# teensy-jst_01.net
KiCad netlist of a schematic drawn in EAGLE
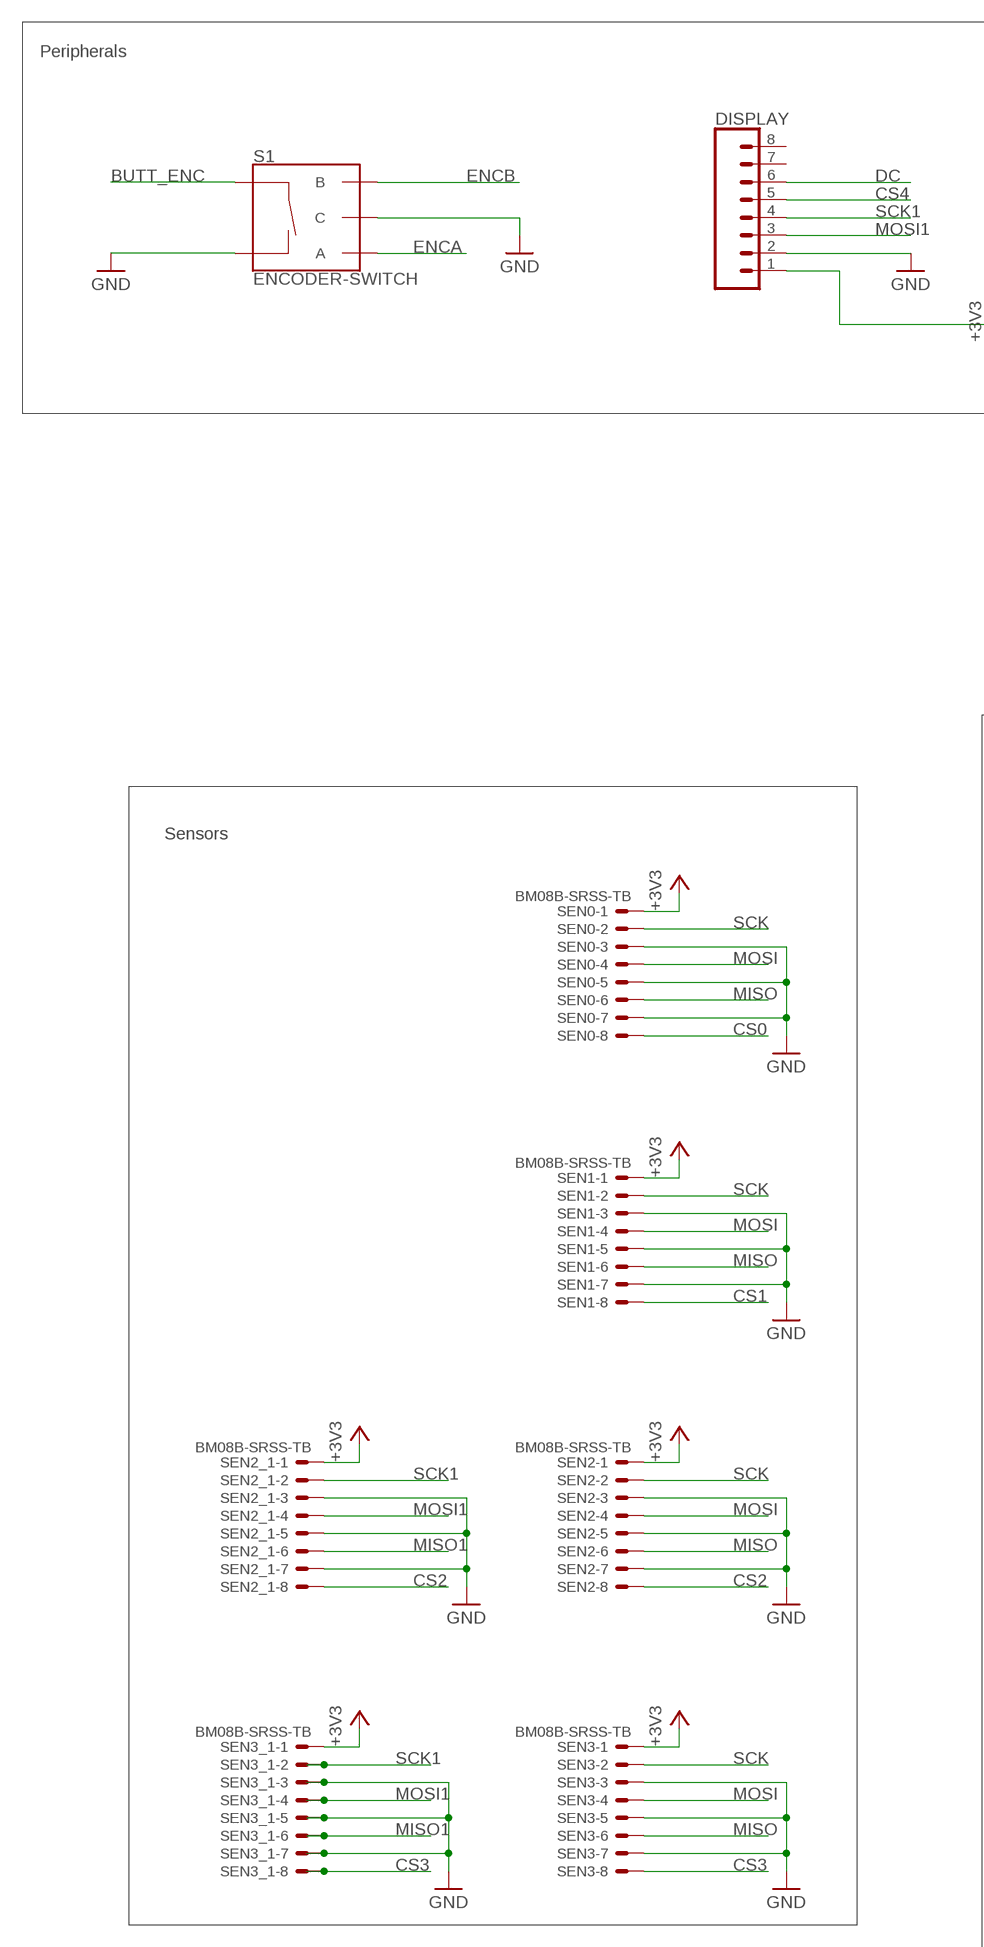
[diagram p0: schematic, sheet 1, part 1 of 2]
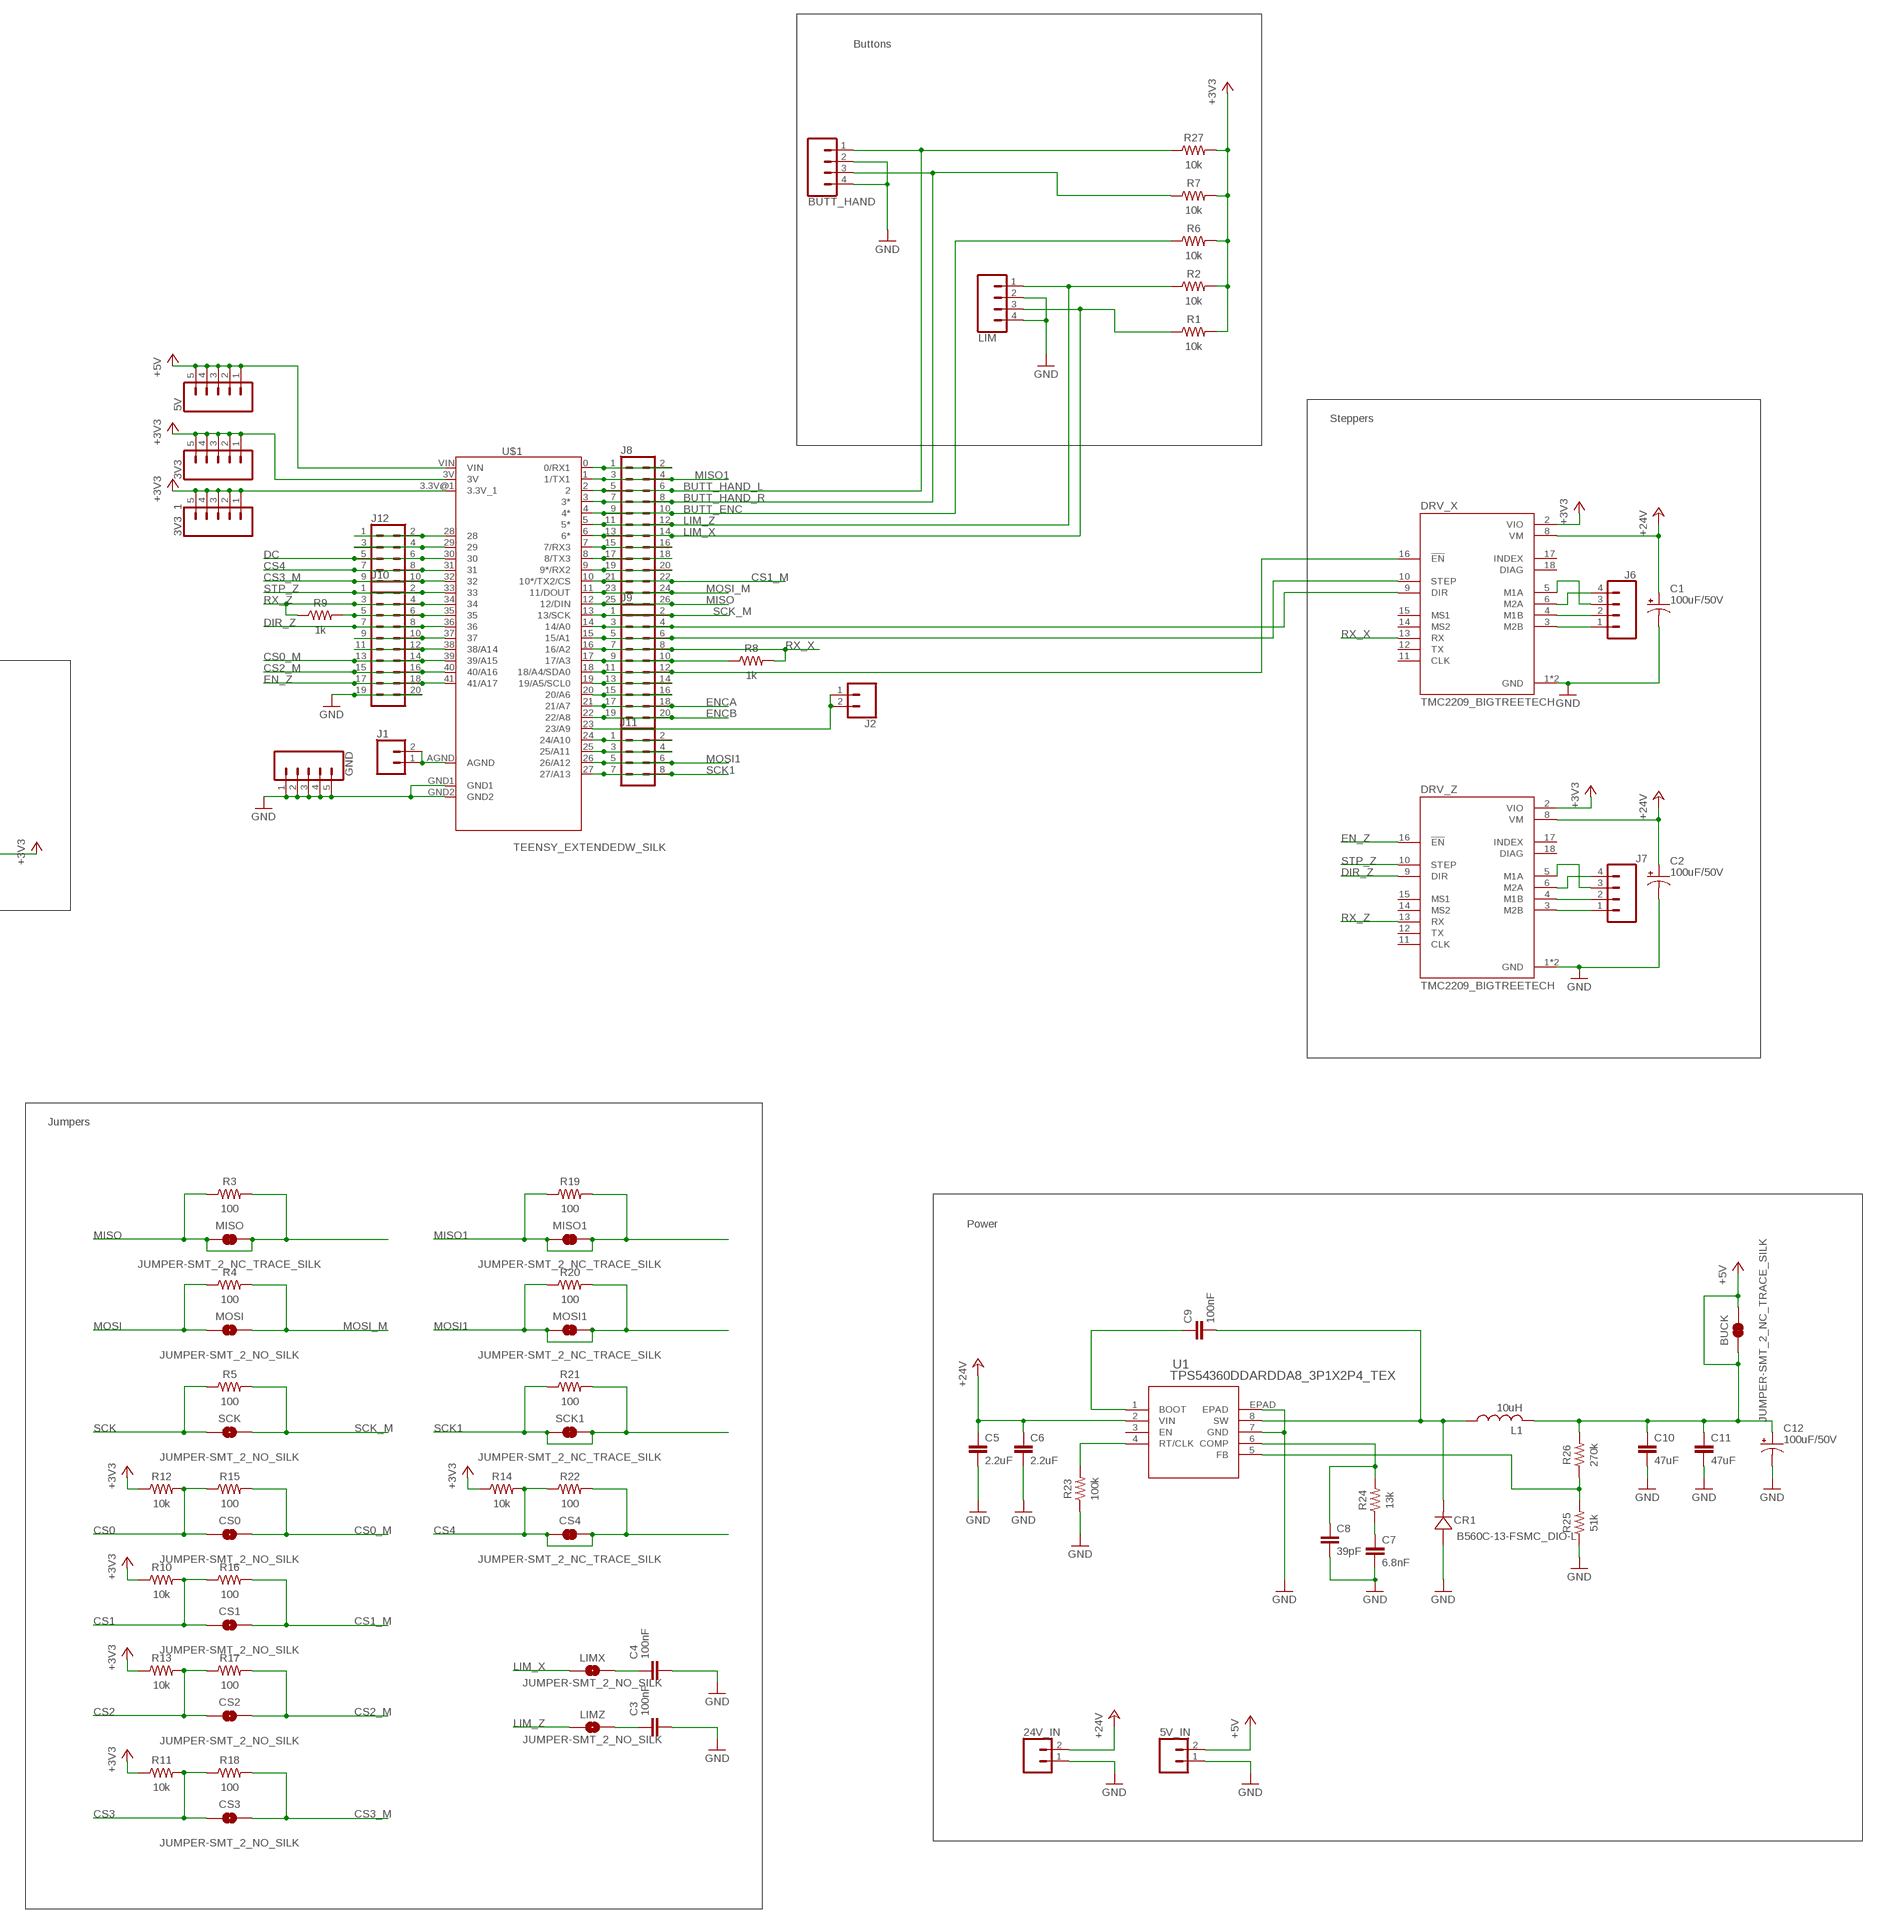
[diagram p1: schematic, sheet 1, part 2 of 2]

(export (version "E")
  (design (tool "Eeschema 10.0.6"))
  (components
    (comp (ref "3V3")
      (value "CONN_05PTH")
      (footprint "eagle-import:1X05")
      (libsource (lib "eagle-import") (part "CONN_05PTH"))
    )
    (comp (ref "3V3_1")
      (value "CONN_05PTH")
      (footprint "eagle-import:1X05")
      (libsource (lib "eagle-import") (part "CONN_05PTH"))
    )
    (comp (ref "5V")
      (value "CONN_05PTH")
      (footprint "eagle-import:1X05")
      (libsource (lib "eagle-import") (part "CONN_05PTH"))
    )
    (comp (ref "5V_IN")
      (value "CONN_025MM")
      (footprint "eagle-import:SCREWTERMINAL-5MM-2")
      (libsource (lib "eagle-import") (part "CONN_025MM"))
    )
    (comp (ref "24V_IN")
      (value "CONN_025MM")
      (footprint "eagle-import:SCREWTERMINAL-5MM-2")
      (libsource (lib "eagle-import") (part "CONN_025MM"))
    )
    (comp (ref "BUCK")
      (value "JUMPER-SMT_2_NC_TRACE_SILK")
      (footprint "eagle-import:SMT-JUMPER_2_NC_TRACE_SILK")
      (libsource (lib "eagle-import") (part "JUMPER-SMT_2_NC_TRACE_SILK"))
    )
    (comp (ref "BUTT_HAND")
      (value "CONN_041X04_NO_SILK")
      (footprint "eagle-import:1X04_NO_SILK")
      (libsource (lib "eagle-import") (part "CONN_041X04_NO_SILK"))
    )
    (comp (ref "C1")
      (value "100uF/50V")
      (footprint "eagle-import:E5-6")
      (libsource (lib "eagle-import") (part "CPOL-USE5-6"))
    )
    (comp (ref "C2")
      (value "100uF/50V")
      (footprint "eagle-import:E5-6")
      (libsource (lib "eagle-import") (part "CPOL-USE5-6"))
    )
    (comp (ref "C3")
      (value "100nF")
      (footprint "eagle-import:C0603")
      (libsource (lib "eagle-import") (part "C-EUC0603"))
    )
    (comp (ref "C4")
      (value "100nF")
      (footprint "eagle-import:C0603")
      (libsource (lib "eagle-import") (part "C-EUC0603"))
    )
    (comp (ref "C5")
      (value "2.2uF")
      (footprint "eagle-import:C0603")
      (libsource (lib "eagle-import") (part "C-EUC0603"))
    )
    (comp (ref "C6")
      (value "2.2uF")
      (footprint "eagle-import:C0603")
      (libsource (lib "eagle-import") (part "C-EUC0603"))
    )
    (comp (ref "C7")
      (value "6.8nF")
      (footprint "eagle-import:C0402")
      (libsource (lib "eagle-import") (part "C-EUC0402"))
    )
    (comp (ref "C8")
      (value "39pF")
      (footprint "eagle-import:C0402")
      (libsource (lib "eagle-import") (part "C-EUC0402"))
    )
    (comp (ref "C9")
      (value "100nF")
      (footprint "eagle-import:C0402")
      (libsource (lib "eagle-import") (part "C-EUC0402"))
    )
    (comp (ref "C10")
      (value "47uF")
      (footprint "eagle-import:C0603")
      (libsource (lib "eagle-import") (part "C-EUC0603"))
    )
    (comp (ref "C11")
      (value "47uF")
      (footprint "eagle-import:C0603")
      (libsource (lib "eagle-import") (part "C-EUC0603"))
    )
    (comp (ref "C12")
      (value "100uF/50V")
      (footprint "eagle-import:E5-6")
      (libsource (lib "eagle-import") (part "CPOL-USE5-6"))
    )
    (comp (ref "CR1")
      (value "B560C-13-FSMC_DIO-L")
      (footprint "eagle-import:SMC_DIO-L")
      (fields
        (field (name "MANUFACTURER_PART_NUMBER") "B560C-13-F")
        (field (name "COPYRIGHT") "Copyright (C) 2024 Ultra Librarian. All rights reserved.")
      )
      (libsource (lib "eagle-import") (part "B560C-13-FSMC_DIO-L"))
    )
    (comp (ref "CS0")
      (value "JUMPER-SMT_2_NO_SILK")
      (footprint "eagle-import:SMT-JUMPER_2_NO_SILK")
      (libsource (lib "eagle-import") (part "JUMPER-SMT_2_NO_SILK"))
    )
    (comp (ref "CS1")
      (value "JUMPER-SMT_2_NO_SILK")
      (footprint "eagle-import:SMT-JUMPER_2_NO_SILK")
      (libsource (lib "eagle-import") (part "JUMPER-SMT_2_NO_SILK"))
    )
    (comp (ref "CS2")
      (value "JUMPER-SMT_2_NO_SILK")
      (footprint "eagle-import:SMT-JUMPER_2_NO_SILK")
      (libsource (lib "eagle-import") (part "JUMPER-SMT_2_NO_SILK"))
    )
    (comp (ref "CS3")
      (value "JUMPER-SMT_2_NO_SILK")
      (footprint "eagle-import:SMT-JUMPER_2_NO_SILK")
      (libsource (lib "eagle-import") (part "JUMPER-SMT_2_NO_SILK"))
    )
    (comp (ref "CS4")
      (value "JUMPER-SMT_2_NC_TRACE_SILK")
      (footprint "eagle-import:SMT-JUMPER_2_NC_TRACE_SILK")
      (libsource (lib "eagle-import") (part "JUMPER-SMT_2_NC_TRACE_SILK"))
    )
    (comp (ref "DISPLAY")
      (value "CONN_08\"")
      (footprint "eagle-import:1X08")
      (libsource (lib "eagle-import") (part "CONN_08{dblquote}"))
    )
    (comp (ref "DRV_X")
      (value "TMC2209_BIGTREETECH")
      (footprint "eagle-import:MODULE_TMC2209_BIGTREETECH")
      (fields
        (field (name "MF") "Trinamic Motion Control GmbH")
        (field (name "MP") "TMC2209 SILENTSTEPSTICK")
      )
      (libsource (lib "eagle-import") (part "TMC2209_BIGTREETECH"))
    )
    (comp (ref "DRV_Z")
      (value "TMC2209_BIGTREETECH")
      (footprint "eagle-import:MODULE_TMC2209_BIGTREETECH")
      (fields
        (field (name "MF") "Trinamic Motion Control GmbH")
        (field (name "MP") "TMC2209 SILENTSTEPSTICK")
      )
      (libsource (lib "eagle-import") (part "TMC2209_BIGTREETECH"))
    )
    (comp (ref "GND")
      (value "CONN_05PTH")
      (footprint "eagle-import:1X05")
      (libsource (lib "eagle-import") (part "CONN_05PTH"))
    )
    (comp (ref "J1")
      (value "CONN_02")
      (footprint "eagle-import:1X02")
      (libsource (lib "eagle-import") (part "CONN_02"))
    )
    (comp (ref "J2")
      (value "CONN_02")
      (footprint "eagle-import:1X02")
      (libsource (lib "eagle-import") (part "CONN_02"))
    )
    (comp (ref "J6")
      (value "CONN_04PTH")
      (footprint "eagle-import:1X04")
      (libsource (lib "eagle-import") (part "CONN_04PTH"))
    )
    (comp (ref "J7")
      (value "CONN_04PTH")
      (footprint "eagle-import:1X04")
      (libsource (lib "eagle-import") (part "CONN_04PTH"))
    )
    (comp (ref "J8")
      (value "CONN_13X22X13")
      (footprint "eagle-import:2X13")
      (libsource (lib "eagle-import") (part "CONN_13X22X13"))
    )
    (comp (ref "J9")
      (value "CONN_10X2")
      (footprint "eagle-import:2X10")
      (libsource (lib "eagle-import") (part "CONN_10X2"))
    )
    (comp (ref "J10")
      (value "CONN_10X2")
      (footprint "eagle-import:2X10")
      (libsource (lib "eagle-import") (part "CONN_10X2"))
    )
    (comp (ref "J11")
      (value "CONN_04X2")
      (footprint "eagle-import:2X4")
      (libsource (lib "eagle-import") (part "CONN_04X2"))
    )
    (comp (ref "J12")
      (value "CONN_05X2PTH")
      (footprint "eagle-import:2X5")
      (libsource (lib "eagle-import") (part "CONN_05X2PTH"))
    )
    (comp (ref "L1")
      (value "10uH")
      (footprint "eagle-import:MWSA0503S-100MT")
      (libsource (lib "eagle-import") (part "L-USMWSA0503S-100MT"))
    )
    (comp (ref "LIM")
      (value "CONN_041X04_NO_SILK")
      (footprint "eagle-import:1X04_NO_SILK")
      (libsource (lib "eagle-import") (part "CONN_041X04_NO_SILK"))
    )
    (comp (ref "LIMX")
      (value "JUMPER-SMT_2_NO_SILK")
      (footprint "eagle-import:SMT-JUMPER_2_NO_SILK")
      (libsource (lib "eagle-import") (part "JUMPER-SMT_2_NO_SILK"))
    )
    (comp (ref "LIMZ")
      (value "JUMPER-SMT_2_NO_SILK")
      (footprint "eagle-import:SMT-JUMPER_2_NO_SILK")
      (libsource (lib "eagle-import") (part "JUMPER-SMT_2_NO_SILK"))
    )
    (comp (ref "MISO")
      (value "JUMPER-SMT_2_NC_TRACE_SILK")
      (footprint "eagle-import:SMT-JUMPER_2_NC_TRACE_SILK")
      (libsource (lib "eagle-import") (part "JUMPER-SMT_2_NC_TRACE_SILK"))
    )
    (comp (ref "MISO1")
      (value "JUMPER-SMT_2_NC_TRACE_SILK")
      (footprint "eagle-import:SMT-JUMPER_2_NC_TRACE_SILK")
      (libsource (lib "eagle-import") (part "JUMPER-SMT_2_NC_TRACE_SILK"))
    )
    (comp (ref "MOSI")
      (value "JUMPER-SMT_2_NO_SILK")
      (footprint "eagle-import:SMT-JUMPER_2_NO_SILK")
      (libsource (lib "eagle-import") (part "JUMPER-SMT_2_NO_SILK"))
    )
    (comp (ref "MOSI1")
      (value "JUMPER-SMT_2_NC_TRACE_SILK")
      (footprint "eagle-import:SMT-JUMPER_2_NC_TRACE_SILK")
      (libsource (lib "eagle-import") (part "JUMPER-SMT_2_NC_TRACE_SILK"))
    )
    (comp (ref "R1")
      (value "10k")
      (footprint "eagle-import:RESC1608X60")
      (libsource (lib "eagle-import") (part "R-USCHIP-0603(1608-METRIC)_"))
    )
    (comp (ref "R2")
      (value "10k")
      (footprint "eagle-import:RESC1608X60")
      (libsource (lib "eagle-import") (part "R-USCHIP-0603(1608-METRIC)_"))
    )
    (comp (ref "R3")
      (value "100")
      (footprint "eagle-import:RESC1608X60")
      (libsource (lib "eagle-import") (part "R-USCHIP-0603(1608-METRIC)_"))
    )
    (comp (ref "R4")
      (value "100")
      (footprint "eagle-import:RESC1608X60")
      (libsource (lib "eagle-import") (part "R-USCHIP-0603(1608-METRIC)_"))
    )
    (comp (ref "R5")
      (value "100")
      (footprint "eagle-import:RESC1608X60")
      (libsource (lib "eagle-import") (part "R-USCHIP-0603(1608-METRIC)_"))
    )
    (comp (ref "R6")
      (value "10k")
      (footprint "eagle-import:RESC1608X60")
      (libsource (lib "eagle-import") (part "R-USCHIP-0603(1608-METRIC)_"))
    )
    (comp (ref "R7")
      (value "10k")
      (footprint "eagle-import:RESC1608X60")
      (libsource (lib "eagle-import") (part "R-USCHIP-0603(1608-METRIC)_"))
    )
    (comp (ref "R8")
      (value "1k")
      (footprint "eagle-import:RESC1608X60")
      (libsource (lib "eagle-import") (part "R-USCHIP-0603(1608-METRIC)_"))
    )
    (comp (ref "R9")
      (value "1k")
      (footprint "eagle-import:RESC1608X60")
      (libsource (lib "eagle-import") (part "R-USCHIP-0603(1608-METRIC)_"))
    )
    (comp (ref "R10")
      (value "10k")
      (footprint "eagle-import:RESC1608X60")
      (libsource (lib "eagle-import") (part "R-USCHIP-0603(1608-METRIC)_"))
    )
    (comp (ref "R11")
      (value "10k")
      (footprint "eagle-import:RESC1608X60")
      (libsource (lib "eagle-import") (part "R-USCHIP-0603(1608-METRIC)_"))
    )
    (comp (ref "R12")
      (value "10k")
      (footprint "eagle-import:RESC1608X60")
      (libsource (lib "eagle-import") (part "R-USCHIP-0603(1608-METRIC)_"))
    )
    (comp (ref "R13")
      (value "10k")
      (footprint "eagle-import:RESC1608X60")
      (libsource (lib "eagle-import") (part "R-USCHIP-0603(1608-METRIC)_"))
    )
    (comp (ref "R14")
      (value "10k")
      (footprint "eagle-import:RESC1608X60")
      (libsource (lib "eagle-import") (part "R-USCHIP-0603(1608-METRIC)_"))
    )
    (comp (ref "R15")
      (value "100")
      (footprint "eagle-import:RESC1608X60")
      (libsource (lib "eagle-import") (part "R-USCHIP-0603(1608-METRIC)_"))
    )
    (comp (ref "R16")
      (value "100")
      (footprint "eagle-import:RESC1608X60")
      (libsource (lib "eagle-import") (part "R-USCHIP-0603(1608-METRIC)_"))
    )
    (comp (ref "R17")
      (value "100")
      (footprint "eagle-import:RESC1608X60")
      (libsource (lib "eagle-import") (part "R-USCHIP-0603(1608-METRIC)_"))
    )
    (comp (ref "R18")
      (value "100")
      (footprint "eagle-import:RESC1608X60")
      (libsource (lib "eagle-import") (part "R-USCHIP-0603(1608-METRIC)_"))
    )
    (comp (ref "R19")
      (value "100")
      (footprint "eagle-import:RESC1608X60")
      (libsource (lib "eagle-import") (part "R-USCHIP-0603(1608-METRIC)_"))
    )
    (comp (ref "R20")
      (value "100")
      (footprint "eagle-import:RESC1608X60")
      (libsource (lib "eagle-import") (part "R-USCHIP-0603(1608-METRIC)_"))
    )
    (comp (ref "R21")
      (value "100")
      (footprint "eagle-import:RESC1608X60")
      (libsource (lib "eagle-import") (part "R-USCHIP-0603(1608-METRIC)_"))
    )
    (comp (ref "R22")
      (value "100")
      (footprint "eagle-import:RESC1608X60")
      (libsource (lib "eagle-import") (part "R-USCHIP-0603(1608-METRIC)_"))
    )
    (comp (ref "R23")
      (value "100k")
      (footprint "eagle-import:RESC1005X40")
      (libsource (lib "eagle-import") (part "R-USCHIP-0402(1005-METRIC)_"))
    )
    (comp (ref "R24")
      (value "13k")
      (footprint "eagle-import:RESC1005X40")
      (libsource (lib "eagle-import") (part "R-USCHIP-0402(1005-METRIC)_"))
    )
    (comp (ref "R25")
      (value "51k")
      (footprint "eagle-import:RESC1005X40")
      (libsource (lib "eagle-import") (part "R-USCHIP-0402(1005-METRIC)_"))
    )
    (comp (ref "R26")
      (value "270k")
      (footprint "eagle-import:RESC1005X40")
      (libsource (lib "eagle-import") (part "R-USCHIP-0402(1005-METRIC)_"))
    )
    (comp (ref "R27")
      (value "10k")
      (footprint "eagle-import:RESC1608X60")
      (libsource (lib "eagle-import") (part "R-USCHIP-0603(1608-METRIC)_"))
    )
    (comp (ref "S1")
      (value "ENCODER-SWITCH")
      (footprint "eagle-import:ROTARY_ENC_PLAIN")
      (libsource (lib "eagle-import") (part "ENCODER-SWITCH"))
    )
    (comp (ref "SCK")
      (value "JUMPER-SMT_2_NO_SILK")
      (footprint "eagle-import:SMT-JUMPER_2_NO_SILK")
      (libsource (lib "eagle-import") (part "JUMPER-SMT_2_NO_SILK"))
    )
    (comp (ref "SCK1")
      (value "JUMPER-SMT_2_NC_TRACE_SILK")
      (footprint "eagle-import:SMT-JUMPER_2_NC_TRACE_SILK")
      (libsource (lib "eagle-import") (part "JUMPER-SMT_2_NC_TRACE_SILK"))
    )
    (comp (ref "SEN0")
      (value "BM08B-SRSS-TB")
      (footprint "eagle-import:BM08B-SRSS-TB")
      (libsource (lib "eagle-import") (part "?M08B-SRSS-TBB"))
    )
    (comp (ref "SEN1")
      (value "BM08B-SRSS-TB")
      (footprint "eagle-import:BM08B-SRSS-TB")
      (libsource (lib "eagle-import") (part "?M08B-SRSS-TBB"))
    )
    (comp (ref "SEN2")
      (value "BM08B-SRSS-TB")
      (footprint "eagle-import:BM08B-SRSS-TB")
      (libsource (lib "eagle-import") (part "?M08B-SRSS-TBB"))
    )
    (comp (ref "SEN2_1")
      (value "BM08B-SRSS-TB")
      (footprint "eagle-import:BM08B-SRSS-TB")
      (libsource (lib "eagle-import") (part "?M08B-SRSS-TBB"))
    )
    (comp (ref "SEN3")
      (value "BM08B-SRSS-TB")
      (footprint "eagle-import:BM08B-SRSS-TB")
      (libsource (lib "eagle-import") (part "?M08B-SRSS-TBB"))
    )
    (comp (ref "SEN3_1")
      (value "BM08B-SRSS-TB")
      (footprint "eagle-import:BM08B-SRSS-TB")
      (libsource (lib "eagle-import") (part "?M08B-SRSS-TBB"))
    )
    (comp (ref "U$1")
      (value "TEENSY_EXTENDEDW_SILK")
      (footprint "eagle-import:TEENSY_EXTENDED")
      (libsource (lib "eagle-import") (part "TEENSY_EXTENDEDW_SILK"))
    )
    (comp (ref "U1")
      (value "TPS54360DDARDDA8_3P1X2P4_TEX")
      (footprint "eagle-import:DDA8_3P1X2P4_TEX")
      (fields
        (field (name "MANUFACTURER_PART_NUMBER") "TPS54360DDAR")
        (field (name "COPYRIGHT") "Copyright (C) 2024 Ultra Librarian. All rights reserved.")
      )
      (libsource (lib "eagle-import") (part "TPS54360DDARDDA8_3P1X2P4_TEX"))
    )
  )
  (nets
    (net (code "1") (name "+3V3") (class "Default")
      (node (ref "3V3") (pin "1") (pinfunction "1_1") (pintype "passive"))
      (node (ref "3V3") (pin "2") (pinfunction "2_2") (pintype "passive"))
      (node (ref "3V3") (pin "3") (pinfunction "3_3") (pintype "passive"))
      (node (ref "3V3") (pin "4") (pinfunction "4_4") (pintype "passive"))
      (node (ref "3V3") (pin "5") (pinfunction "5_5") (pintype "passive"))
      (node (ref "3V3_1") (pin "1") (pinfunction "1_1") (pintype "passive"))
      (node (ref "3V3_1") (pin "2") (pinfunction "2_2") (pintype "passive"))
      (node (ref "3V3_1") (pin "3") (pinfunction "3_3") (pintype "passive"))
      (node (ref "3V3_1") (pin "4") (pinfunction "4_4") (pintype "passive"))
      (node (ref "3V3_1") (pin "5") (pinfunction "5_5") (pintype "passive"))
      (node (ref "DISPLAY") (pin "1") (pinfunction "1_1") (pintype "passive"))
      (node (ref "DRV_X") (pin "2") (pinfunction "VIO_2") (pintype "power_in"))
      (node (ref "DRV_Z") (pin "2") (pinfunction "VIO_2") (pintype "power_in"))
      (node (ref "R1") (pin "2") (pinfunction "2_2") (pintype "passive"))
      (node (ref "R10") (pin "1") (pinfunction "1_1") (pintype "passive"))
      (node (ref "R11") (pin "1") (pinfunction "1_1") (pintype "passive"))
      (node (ref "R12") (pin "1") (pinfunction "1_1") (pintype "passive"))
      (node (ref "R13") (pin "1") (pinfunction "1_1") (pintype "passive"))
      (node (ref "R14") (pin "1") (pinfunction "1_1") (pintype "passive"))
      (node (ref "R2") (pin "2") (pinfunction "2_2") (pintype "passive"))
      (node (ref "R27") (pin "2") (pinfunction "2_2") (pintype "passive"))
      (node (ref "R6") (pin "2") (pinfunction "2_2") (pintype "passive"))
      (node (ref "R7") (pin "2") (pinfunction "2_2") (pintype "passive"))
      (node (ref "SEN0") (pin "1") (pinfunction "S_1") (pintype "passive"))
      (node (ref "SEN1") (pin "1") (pinfunction "S_1") (pintype "passive"))
      (node (ref "SEN2") (pin "1") (pinfunction "S_1") (pintype "passive"))
      (node (ref "SEN2_1") (pin "1") (pinfunction "S_1") (pintype "passive"))
      (node (ref "SEN3") (pin "1") (pinfunction "S_1") (pintype "passive"))
      (node (ref "SEN3_1") (pin "1") (pinfunction "S_1") (pintype "passive"))
      (node (ref "U$1") (pin "3.3V@1") (pinfunction "3.3V_1_3.3V@1") (pintype "power_in"))
      (node (ref "U$1") (pin "3V") (pinfunction "3V_3V") (pintype "power_in"))
    )
    (net (code "2") (name "+5V") (class "Default")
      (node (ref "5V") (pin "1") (pinfunction "1_1") (pintype "passive"))
      (node (ref "5V") (pin "2") (pinfunction "2_2") (pintype "passive"))
      (node (ref "5V") (pin "3") (pinfunction "3_3") (pintype "passive"))
      (node (ref "5V") (pin "4") (pinfunction "4_4") (pintype "passive"))
      (node (ref "5V") (pin "5") (pinfunction "5_5") (pintype "passive"))
      (node (ref "5V_IN") (pin "2") (pinfunction "2_2") (pintype "passive"))
      (node (ref "BUCK") (pin "1") (pinfunction "1_1") (pintype "passive"))
      (node (ref "BUCK") (pin "2") (pinfunction "2_2") (pintype "passive"))
      (node (ref "C10") (pin "1") (pinfunction "1_1") (pintype "passive"))
      (node (ref "C11") (pin "1") (pinfunction "1_1") (pintype "passive"))
      (node (ref "C12") (pin "+") (pinfunction "+_+") (pintype "passive"))
      (node (ref "L1") (pin "2") (pinfunction "2_2") (pintype "passive"))
      (node (ref "R26") (pin "2") (pinfunction "2_2") (pintype "passive"))
      (node (ref "U$1") (pin "VIN") (pinfunction "VIN_VIN") (pintype "power_in"))
    )
    (net (code "3") (name "+24V") (class "Default")
      (node (ref "24V_IN") (pin "2") (pinfunction "2_2") (pintype "passive"))
      (node (ref "C1") (pin "+") (pinfunction "+_+") (pintype "passive"))
      (node (ref "C2") (pin "+") (pinfunction "+_+") (pintype "passive"))
      (node (ref "C5") (pin "1") (pinfunction "1_1") (pintype "passive"))
      (node (ref "C6") (pin "1") (pinfunction "1_1") (pintype "passive"))
      (node (ref "DRV_X") (pin "8") (pinfunction "VM_8") (pintype "power_in"))
      (node (ref "DRV_Z") (pin "8") (pinfunction "VM_8") (pintype "power_in"))
      (node (ref "U1") (pin "2") (pinfunction "VIN_2") (pintype "input"))
    )
    (net (code "4") (name "/BUTT_ENC") (class "Default")
      (node (ref "J8") (pin "10") (pinfunction "10_10") (pintype "passive"))
      (node (ref "J8") (pin "9") (pinfunction "9_9") (pintype "passive"))
      (node (ref "R6") (pin "1") (pinfunction "1_1") (pintype "passive"))
      (node (ref "S1") (pin "SW+") (pinfunction "SW+_SW+") (pintype "bidirectional"))
      (node (ref "U$1") (pin "4") (pinfunction "4*_4") (pintype "bidirectional"))
    )
    (net (code "5") (name "/BUTT_HAND_L") (class "Default")
      (node (ref "BUTT_HAND") (pin "1") (pinfunction "1_1") (pintype "passive"))
      (node (ref "J8") (pin "5") (pinfunction "5_5") (pintype "passive"))
      (node (ref "J8") (pin "6") (pinfunction "6_6") (pintype "passive"))
      (node (ref "R27") (pin "1") (pinfunction "1_1") (pintype "passive"))
      (node (ref "U$1") (pin "2") (pinfunction "2_2") (pintype "bidirectional"))
    )
    (net (code "6") (name "/BUTT_HAND_R") (class "Default")
      (node (ref "BUTT_HAND") (pin "3") (pinfunction "3_3") (pintype "passive"))
      (node (ref "J8") (pin "7") (pinfunction "7_7") (pintype "passive"))
      (node (ref "J8") (pin "8") (pinfunction "8_8") (pintype "passive"))
      (node (ref "R7") (pin "1") (pinfunction "1_1") (pintype "passive"))
      (node (ref "U$1") (pin "3") (pinfunction "3*_3") (pintype "bidirectional"))
    )
    (net (code "7") (name "/CS0") (class "Default")
      (node (ref "CS0") (pin "1") (pinfunction "1_1") (pintype "passive"))
      (node (ref "R12") (pin "2") (pinfunction "2_2") (pintype "passive"))
      (node (ref "R15") (pin "1") (pinfunction "1_1") (pintype "passive"))
      (node (ref "SEN0") (pin "8") (pinfunction "S_8") (pintype "passive"))
    )
    (net (code "8") (name "/CS0_M") (class "Default")
      (node (ref "CS0") (pin "2") (pinfunction "2_2") (pintype "passive"))
      (node (ref "J10") (pin "13") (pinfunction "13_13") (pintype "passive"))
      (node (ref "J10") (pin "14") (pinfunction "14_14") (pintype "passive"))
      (node (ref "R15") (pin "2") (pinfunction "2_2") (pintype "passive"))
      (node (ref "U$1") (pin "39") (pinfunction "39/A15_39") (pintype "bidirectional"))
    )
    (net (code "9") (name "/CS1") (class "Default")
      (node (ref "CS1") (pin "1") (pinfunction "1_1") (pintype "passive"))
      (node (ref "R10") (pin "2") (pinfunction "2_2") (pintype "passive"))
      (node (ref "R16") (pin "1") (pinfunction "1_1") (pintype "passive"))
      (node (ref "SEN1") (pin "8") (pinfunction "S_8") (pintype "passive"))
    )
    (net (code "10") (name "/CS1_M") (class "Default")
      (node (ref "CS1") (pin "2") (pinfunction "2_2") (pintype "passive"))
      (node (ref "J8") (pin "21") (pinfunction "21_21") (pintype "passive"))
      (node (ref "J8") (pin "22") (pinfunction "22_22") (pintype "passive"))
      (node (ref "R16") (pin "2") (pinfunction "2_2") (pintype "passive"))
      (node (ref "U$1") (pin "10") (pinfunction "10*/TX2/CS_10") (pintype "bidirectional"))
    )
    (net (code "11") (name "/CS2") (class "Default")
      (node (ref "CS2") (pin "1") (pinfunction "1_1") (pintype "passive"))
      (node (ref "R13") (pin "2") (pinfunction "2_2") (pintype "passive"))
      (node (ref "R17") (pin "1") (pinfunction "1_1") (pintype "passive"))
      (node (ref "SEN2") (pin "8") (pinfunction "S_8") (pintype "passive"))
      (node (ref "SEN2_1") (pin "8") (pinfunction "S_8") (pintype "passive"))
    )
    (net (code "12") (name "/CS2_M") (class "Default")
      (node (ref "CS2") (pin "2") (pinfunction "2_2") (pintype "passive"))
      (node (ref "J10") (pin "15") (pinfunction "15_15") (pintype "passive"))
      (node (ref "J10") (pin "16") (pinfunction "16_16") (pintype "passive"))
      (node (ref "R17") (pin "2") (pinfunction "2_2") (pintype "passive"))
      (node (ref "U$1") (pin "40") (pinfunction "40/A16_40") (pintype "bidirectional"))
    )
    (net (code "13") (name "/CS3") (class "Default")
      (node (ref "CS3") (pin "1") (pinfunction "1_1") (pintype "passive"))
      (node (ref "R11") (pin "2") (pinfunction "2_2") (pintype "passive"))
      (node (ref "R18") (pin "1") (pinfunction "1_1") (pintype "passive"))
      (node (ref "SEN3") (pin "8") (pinfunction "S_8") (pintype "passive"))
      (node (ref "SEN3_1") (pin "8") (pinfunction "S_8") (pintype "passive"))
    )
    (net (code "14") (name "/CS3_M") (class "Default")
      (node (ref "CS3") (pin "2") (pinfunction "2_2") (pintype "passive"))
      (node (ref "J12") (pin "10") (pinfunction "10_10") (pintype "passive"))
      (node (ref "J12") (pin "9") (pinfunction "9_9") (pintype "passive"))
      (node (ref "R18") (pin "2") (pinfunction "2_2") (pintype "passive"))
      (node (ref "U$1") (pin "32") (pinfunction "32_32") (pintype "bidirectional"))
    )
    (net (code "15") (name "/CS4") (class "Default")
      (node (ref "CS4") (pin "1") (pinfunction "1_1") (pintype "passive"))
      (node (ref "CS4") (pin "2") (pinfunction "2_2") (pintype "passive"))
      (node (ref "DISPLAY") (pin "5") (pinfunction "5_5") (pintype "passive"))
      (node (ref "J12") (pin "7") (pinfunction "7_7") (pintype "passive"))
      (node (ref "J12") (pin "8") (pinfunction "8_8") (pintype "passive"))
      (node (ref "R14") (pin "2") (pinfunction "2_2") (pintype "passive"))
      (node (ref "R22") (pin "1") (pinfunction "1_1") (pintype "passive"))
      (node (ref "R22") (pin "2") (pinfunction "2_2") (pintype "passive"))
      (node (ref "U$1") (pin "31") (pinfunction "31_31") (pintype "bidirectional"))
    )
    (net (code "16") (name "/DC") (class "Default")
      (node (ref "DISPLAY") (pin "6") (pinfunction "6_6") (pintype "passive"))
      (node (ref "J12") (pin "5") (pinfunction "5_5") (pintype "passive"))
      (node (ref "J12") (pin "6") (pinfunction "6_6") (pintype "passive"))
      (node (ref "U$1") (pin "30") (pinfunction "30_30") (pintype "bidirectional"))
    )
    (net (code "17") (name "/DIR_Z") (class "Default")
      (node (ref "DRV_Z") (pin "9") (pinfunction "DIR_9") (pintype "input"))
      (node (ref "J10") (pin "7") (pinfunction "7_7") (pintype "passive"))
      (node (ref "J10") (pin "8") (pinfunction "8_8") (pintype "passive"))
      (node (ref "U$1") (pin "36") (pinfunction "36_36") (pintype "bidirectional"))
    )
    (net (code "18") (name "/ENCA") (class "Default")
      (node (ref "J9") (pin "17") (pinfunction "17_17") (pintype "passive"))
      (node (ref "J9") (pin "18") (pinfunction "18_18") (pintype "passive"))
      (node (ref "S1") (pin "A") (pinfunction "A_A") (pintype "bidirectional"))
      (node (ref "U$1") (pin "21") (pinfunction "21/A7_21") (pintype "bidirectional"))
    )
    (net (code "19") (name "/ENCB") (class "Default")
      (node (ref "J9") (pin "19") (pinfunction "19_19") (pintype "passive"))
      (node (ref "J9") (pin "20") (pinfunction "20_20") (pintype "passive"))
      (node (ref "S1") (pin "B") (pinfunction "B_B") (pintype "bidirectional"))
      (node (ref "U$1") (pin "22") (pinfunction "22/A8_22") (pintype "bidirectional"))
    )
    (net (code "20") (name "/EN_Z") (class "Default")
      (node (ref "DRV_Z") (pin "16") (pinfunction "~{EN}_16") (pintype "input"))
      (node (ref "J10") (pin "17") (pinfunction "17_17") (pintype "passive"))
      (node (ref "J10") (pin "18") (pinfunction "18_18") (pintype "passive"))
      (node (ref "U$1") (pin "41") (pinfunction "41/A17_41") (pintype "bidirectional"))
    )
    (net (code "21") (name "/LIM_X") (class "Default")
      (node (ref "J8") (pin "13") (pinfunction "13_13") (pintype "passive"))
      (node (ref "J8") (pin "14") (pinfunction "14_14") (pintype "passive"))
      (node (ref "LIM") (pin "3") (pinfunction "3_3") (pintype "passive"))
      (node (ref "LIMX") (pin "1") (pinfunction "1_1") (pintype "passive"))
      (node (ref "R1") (pin "1") (pinfunction "1_1") (pintype "passive"))
      (node (ref "U$1") (pin "6") (pinfunction "6*_6") (pintype "bidirectional"))
    )
    (net (code "22") (name "/LIM_Z") (class "Default")
      (node (ref "J8") (pin "11") (pinfunction "11_11") (pintype "passive"))
      (node (ref "J8") (pin "12") (pinfunction "12_12") (pintype "passive"))
      (node (ref "LIM") (pin "1") (pinfunction "1_1") (pintype "passive"))
      (node (ref "LIMZ") (pin "1") (pinfunction "1_1") (pintype "passive"))
      (node (ref "R2") (pin "1") (pinfunction "1_1") (pintype "passive"))
      (node (ref "U$1") (pin "5") (pinfunction "5*_5") (pintype "bidirectional"))
    )
    (net (code "23") (name "/MISO") (class "Default")
      (node (ref "J8") (pin "25") (pinfunction "25_25") (pintype "passive"))
      (node (ref "J8") (pin "26") (pinfunction "26_26") (pintype "passive"))
      (node (ref "MISO") (pin "1") (pinfunction "1_1") (pintype "passive"))
      (node (ref "MISO") (pin "2") (pinfunction "2_2") (pintype "passive"))
      (node (ref "R3") (pin "1") (pinfunction "1_1") (pintype "passive"))
      (node (ref "R3") (pin "2") (pinfunction "2_2") (pintype "passive"))
      (node (ref "SEN0") (pin "6") (pinfunction "S_6") (pintype "passive"))
      (node (ref "SEN1") (pin "6") (pinfunction "S_6") (pintype "passive"))
      (node (ref "SEN2") (pin "6") (pinfunction "S_6") (pintype "passive"))
      (node (ref "SEN3") (pin "6") (pinfunction "S_6") (pintype "passive"))
      (node (ref "U$1") (pin "12") (pinfunction "12/DIN_12") (pintype "bidirectional"))
    )
    (net (code "24") (name "/MISO1") (class "Default")
      (node (ref "J8") (pin "3") (pinfunction "3_3") (pintype "passive"))
      (node (ref "J8") (pin "4") (pinfunction "4_4") (pintype "passive"))
      (node (ref "MISO1") (pin "1") (pinfunction "1_1") (pintype "passive"))
      (node (ref "MISO1") (pin "2") (pinfunction "2_2") (pintype "passive"))
      (node (ref "R19") (pin "1") (pinfunction "1_1") (pintype "passive"))
      (node (ref "R19") (pin "2") (pinfunction "2_2") (pintype "passive"))
      (node (ref "SEN2_1") (pin "6") (pinfunction "S_6") (pintype "passive"))
      (node (ref "SEN3_1") (pin "6") (pinfunction "S_6") (pintype "passive"))
      (node (ref "U$1") (pin "1") (pinfunction "1/TX1_1") (pintype "bidirectional"))
    )
    (net (code "25") (name "/MOSI") (class "Default")
      (node (ref "MOSI") (pin "1") (pinfunction "1_1") (pintype "passive"))
      (node (ref "R4") (pin "1") (pinfunction "1_1") (pintype "passive"))
      (node (ref "SEN0") (pin "4") (pinfunction "S_4") (pintype "passive"))
      (node (ref "SEN1") (pin "4") (pinfunction "S_4") (pintype "passive"))
      (node (ref "SEN2") (pin "4") (pinfunction "S_4") (pintype "passive"))
      (node (ref "SEN3") (pin "4") (pinfunction "S_4") (pintype "passive"))
    )
    (net (code "26") (name "/MOSI1") (class "Default")
      (node (ref "DISPLAY") (pin "3") (pinfunction "3_3") (pintype "passive"))
      (node (ref "J11") (pin "5") (pinfunction "5_5") (pintype "passive"))
      (node (ref "J11") (pin "6") (pinfunction "6_6") (pintype "passive"))
      (node (ref "MOSI1") (pin "1") (pinfunction "1_1") (pintype "passive"))
      (node (ref "MOSI1") (pin "2") (pinfunction "2_2") (pintype "passive"))
      (node (ref "R20") (pin "1") (pinfunction "1_1") (pintype "passive"))
      (node (ref "R20") (pin "2") (pinfunction "2_2") (pintype "passive"))
      (node (ref "SEN2_1") (pin "4") (pinfunction "S_4") (pintype "passive"))
      (node (ref "SEN3_1") (pin "4") (pinfunction "S_4") (pintype "passive"))
      (node (ref "U$1") (pin "26") (pinfunction "26/A12_26") (pintype "bidirectional"))
    )
    (net (code "27") (name "/MOSI_M") (class "Default")
      (node (ref "J8") (pin "23") (pinfunction "23_23") (pintype "passive"))
      (node (ref "J8") (pin "24") (pinfunction "24_24") (pintype "passive"))
      (node (ref "MOSI") (pin "2") (pinfunction "2_2") (pintype "passive"))
      (node (ref "R4") (pin "2") (pinfunction "2_2") (pintype "passive"))
      (node (ref "U$1") (pin "11") (pinfunction "11/DOUT_11") (pintype "bidirectional"))
    )
    (net (code "28") (name "/RX_X") (class "Default")
      (node (ref "DRV_X") (pin "13") (pinfunction "RX_13") (pintype "input"))
      (node (ref "J9") (pin "7") (pinfunction "7_7") (pintype "passive"))
      (node (ref "J9") (pin "8") (pinfunction "8_8") (pintype "passive"))
      (node (ref "R8") (pin "2") (pinfunction "2_2") (pintype "passive"))
      (node (ref "U$1") (pin "16") (pinfunction "16/A2_16") (pintype "bidirectional"))
    )
    (net (code "29") (name "/RX_Z") (class "Default")
      (node (ref "DRV_Z") (pin "13") (pinfunction "RX_13") (pintype "input"))
      (node (ref "J10") (pin "3") (pinfunction "3_3") (pintype "passive"))
      (node (ref "J10") (pin "4") (pinfunction "4_4") (pintype "passive"))
      (node (ref "R9") (pin "1") (pinfunction "1_1") (pintype "passive"))
      (node (ref "U$1") (pin "34") (pinfunction "34_34") (pintype "bidirectional"))
    )
    (net (code "30") (name "/SCK") (class "Default")
      (node (ref "R5") (pin "1") (pinfunction "1_1") (pintype "passive"))
      (node (ref "SCK") (pin "1") (pinfunction "1_1") (pintype "passive"))
      (node (ref "SEN0") (pin "2") (pinfunction "S_2") (pintype "passive"))
      (node (ref "SEN1") (pin "2") (pinfunction "S_2") (pintype "passive"))
      (node (ref "SEN2") (pin "2") (pinfunction "S_2") (pintype "passive"))
      (node (ref "SEN3") (pin "2") (pinfunction "S_2") (pintype "passive"))
    )
    (net (code "31") (name "/SCK1") (class "Default")
      (node (ref "DISPLAY") (pin "4") (pinfunction "4_4") (pintype "passive"))
      (node (ref "J11") (pin "7") (pinfunction "7_7") (pintype "passive"))
      (node (ref "J11") (pin "8") (pinfunction "8_8") (pintype "passive"))
      (node (ref "R21") (pin "1") (pinfunction "1_1") (pintype "passive"))
      (node (ref "R21") (pin "2") (pinfunction "2_2") (pintype "passive"))
      (node (ref "SCK1") (pin "1") (pinfunction "1_1") (pintype "passive"))
      (node (ref "SCK1") (pin "2") (pinfunction "2_2") (pintype "passive"))
      (node (ref "SEN2_1") (pin "2") (pinfunction "S_2") (pintype "passive"))
      (node (ref "SEN3_1") (pin "2") (pinfunction "S_2") (pintype "passive"))
      (node (ref "U$1") (pin "27") (pinfunction "27/A13_27") (pintype "bidirectional"))
    )
    (net (code "32") (name "/SCK_M") (class "Default")
      (node (ref "J9") (pin "1") (pinfunction "1_1") (pintype "passive"))
      (node (ref "J9") (pin "2") (pinfunction "2_2") (pintype "passive"))
      (node (ref "R5") (pin "2") (pinfunction "2_2") (pintype "passive"))
      (node (ref "SCK") (pin "2") (pinfunction "2_2") (pintype "passive"))
      (node (ref "U$1") (pin "13") (pinfunction "13/SCK_13") (pintype "bidirectional"))
    )
    (net (code "33") (name "/STP_Z") (class "Default")
      (node (ref "DRV_Z") (pin "10") (pinfunction "STEP_10") (pintype "input"))
      (node (ref "J10") (pin "1") (pinfunction "1_1") (pintype "passive"))
      (node (ref "J10") (pin "2") (pinfunction "2_2") (pintype "passive"))
      (node (ref "U$1") (pin "33") (pinfunction "33_33") (pintype "bidirectional"))
    )
    (net (code "34") (name "GND") (class "Default")
      (node (ref "24V_IN") (pin "1") (pinfunction "1_1") (pintype "passive"))
      (node (ref "5V_IN") (pin "1") (pinfunction "1_1") (pintype "passive"))
      (node (ref "BUTT_HAND") (pin "2") (pinfunction "2_2") (pintype "passive"))
      (node (ref "BUTT_HAND") (pin "4") (pinfunction "4_4") (pintype "passive"))
      (node (ref "C1") (pin "-") (pinfunction "-_-") (pintype "passive"))
      (node (ref "C10") (pin "2") (pinfunction "2_2") (pintype "passive"))
      (node (ref "C11") (pin "2") (pinfunction "2_2") (pintype "passive"))
      (node (ref "C12") (pin "-") (pinfunction "-_-") (pintype "passive"))
      (node (ref "C2") (pin "-") (pinfunction "-_-") (pintype "passive"))
      (node (ref "C3") (pin "2") (pinfunction "2_2") (pintype "passive"))
      (node (ref "C4") (pin "2") (pinfunction "2_2") (pintype "passive"))
      (node (ref "C5") (pin "2") (pinfunction "2_2") (pintype "passive"))
      (node (ref "C6") (pin "2") (pinfunction "2_2") (pintype "passive"))
      (node (ref "C7") (pin "2") (pinfunction "2_2") (pintype "passive"))
      (node (ref "C8") (pin "2") (pinfunction "2_2") (pintype "passive"))
      (node (ref "CR1") (pin "2") (pinfunction "2_2") (pintype "passive"))
      (node (ref "DISPLAY") (pin "2") (pinfunction "2_2") (pintype "passive"))
      (node (ref "DRV_X") (pin "1") (pinfunction "GND_1") (pintype "power_in"))
      (node (ref "DRV_X") (pin "7") (pinfunction "GND_7") (pintype "power_in"))
      (node (ref "DRV_Z") (pin "1") (pinfunction "GND_1") (pintype "power_in"))
      (node (ref "DRV_Z") (pin "7") (pinfunction "GND_7") (pintype "power_in"))
      (node (ref "GND") (pin "1") (pinfunction "1_1") (pintype "passive"))
      (node (ref "GND") (pin "2") (pinfunction "2_2") (pintype "passive"))
      (node (ref "GND") (pin "3") (pinfunction "3_3") (pintype "passive"))
      (node (ref "GND") (pin "4") (pinfunction "4_4") (pintype "passive"))
      (node (ref "GND") (pin "5") (pinfunction "5_5") (pintype "passive"))
      (node (ref "J10") (pin "19") (pinfunction "19_19") (pintype "passive"))
      (node (ref "J10") (pin "20") (pinfunction "20_20") (pintype "passive"))
      (node (ref "LIM") (pin "2") (pinfunction "2_2") (pintype "passive"))
      (node (ref "LIM") (pin "4") (pinfunction "4_4") (pintype "passive"))
      (node (ref "R23") (pin "1") (pinfunction "1_1") (pintype "passive"))
      (node (ref "R25") (pin "1") (pinfunction "1_1") (pintype "passive"))
      (node (ref "S1") (pin "C") (pinfunction "C_C") (pintype "bidirectional"))
      (node (ref "S1") (pin "SW-") (pinfunction "SW-_SW-") (pintype "bidirectional"))
      (node (ref "SEN0") (pin "3") (pinfunction "S_3") (pintype "passive"))
      (node (ref "SEN0") (pin "5") (pinfunction "S_5") (pintype "passive"))
      (node (ref "SEN0") (pin "7") (pinfunction "S_7") (pintype "passive"))
      (node (ref "SEN1") (pin "3") (pinfunction "S_3") (pintype "passive"))
      (node (ref "SEN1") (pin "5") (pinfunction "S_5") (pintype "passive"))
      (node (ref "SEN1") (pin "7") (pinfunction "S_7") (pintype "passive"))
      (node (ref "SEN2") (pin "3") (pinfunction "S_3") (pintype "passive"))
      (node (ref "SEN2") (pin "5") (pinfunction "S_5") (pintype "passive"))
      (node (ref "SEN2") (pin "7") (pinfunction "S_7") (pintype "passive"))
      (node (ref "SEN2_1") (pin "3") (pinfunction "S_3") (pintype "passive"))
      (node (ref "SEN2_1") (pin "5") (pinfunction "S_5") (pintype "passive"))
      (node (ref "SEN2_1") (pin "7") (pinfunction "S_7") (pintype "passive"))
      (node (ref "SEN3") (pin "3") (pinfunction "S_3") (pintype "passive"))
      (node (ref "SEN3") (pin "5") (pinfunction "S_5") (pintype "passive"))
      (node (ref "SEN3") (pin "7") (pinfunction "S_7") (pintype "passive"))
      (node (ref "SEN3_1") (pin "3") (pinfunction "S_3") (pintype "passive"))
      (node (ref "SEN3_1") (pin "5") (pinfunction "S_5") (pintype "passive"))
      (node (ref "SEN3_1") (pin "7") (pinfunction "S_7") (pintype "passive"))
      (node (ref "U$1") (pin "GND1") (pinfunction "GND1_GND1") (pintype "power_in"))
      (node (ref "U$1") (pin "GND2") (pinfunction "GND2_GND2") (pintype "power_in"))
      (node (ref "U1") (pin "7") (pinfunction "GND_7") (pintype "power_in"))
      (node (ref "U1") (pin "EPAD") (pinfunction "EPAD_EPAD") (pintype "passive"))
    )
    (net (code "35") (name "Net-(C3-Pad1)") (class "Default")
      (node (ref "C3") (pin "1") (pinfunction "1_1") (pintype "passive"))
      (node (ref "LIMZ") (pin "2") (pinfunction "2_2") (pintype "passive"))
    )
    (net (code "36") (name "Net-(C4-Pad1)") (class "Default")
      (node (ref "C4") (pin "1") (pinfunction "1_1") (pintype "passive"))
      (node (ref "LIMX") (pin "2") (pinfunction "2_2") (pintype "passive"))
    )
    (net (code "37") (name "Net-(C7-Pad1)") (class "Default")
      (node (ref "C7") (pin "1") (pinfunction "1_1") (pintype "passive"))
      (node (ref "R24") (pin "1") (pinfunction "1_1") (pintype "passive"))
    )
    (net (code "38") (name "Net-(DRV_X-DIR)") (class "Default")
      (node (ref "DRV_X") (pin "9") (pinfunction "DIR_9") (pintype "input"))
      (node (ref "J9") (pin "3") (pinfunction "3_3") (pintype "passive"))
      (node (ref "J9") (pin "4") (pinfunction "4_4") (pintype "passive"))
      (node (ref "U$1") (pin "14") (pinfunction "14/A0_14") (pintype "bidirectional"))
    )
    (net (code "39") (name "Net-(DRV_X-M1A)") (class "Default")
      (node (ref "DRV_X") (pin "5") (pinfunction "M1A_5") (pintype "output"))
      (node (ref "J6") (pin "3") (pinfunction "3_3") (pintype "passive"))
    )
    (net (code "40") (name "Net-(DRV_X-M1B)") (class "Default")
      (node (ref "DRV_X") (pin "4") (pinfunction "M1B_4") (pintype "output"))
      (node (ref "J6") (pin "2") (pinfunction "2_2") (pintype "passive"))
    )
    (net (code "41") (name "Net-(DRV_X-M2A)") (class "Default")
      (node (ref "DRV_X") (pin "6") (pinfunction "M2A_6") (pintype "output"))
      (node (ref "J6") (pin "4") (pinfunction "4_4") (pintype "passive"))
    )
    (net (code "42") (name "Net-(DRV_X-M2B)") (class "Default")
      (node (ref "DRV_X") (pin "3") (pinfunction "M2B_3") (pintype "output"))
      (node (ref "J6") (pin "1") (pinfunction "1_1") (pintype "passive"))
    )
    (net (code "43") (name "Net-(DRV_X-STEP)") (class "Default")
      (node (ref "DRV_X") (pin "10") (pinfunction "STEP_10") (pintype "input"))
      (node (ref "J9") (pin "5") (pinfunction "5_5") (pintype "passive"))
      (node (ref "J9") (pin "6") (pinfunction "6_6") (pintype "passive"))
      (node (ref "U$1") (pin "15") (pinfunction "15/A1_15") (pintype "bidirectional"))
    )
    (net (code "44") (name "Net-(DRV_X-~{EN})") (class "Default")
      (node (ref "DRV_X") (pin "16") (pinfunction "~{EN}_16") (pintype "input"))
      (node (ref "J9") (pin "11") (pinfunction "11_11") (pintype "passive"))
      (node (ref "J9") (pin "12") (pinfunction "12_12") (pintype "passive"))
      (node (ref "U$1") (pin "18") (pinfunction "18/A4/SDA0_18") (pintype "bidirectional"))
    )
    (net (code "45") (name "Net-(DRV_Z-M1A)") (class "Default")
      (node (ref "DRV_Z") (pin "5") (pinfunction "M1A_5") (pintype "output"))
      (node (ref "J7") (pin "3") (pinfunction "3_3") (pintype "passive"))
    )
    (net (code "46") (name "Net-(DRV_Z-M1B)") (class "Default")
      (node (ref "DRV_Z") (pin "4") (pinfunction "M1B_4") (pintype "output"))
      (node (ref "J7") (pin "2") (pinfunction "2_2") (pintype "passive"))
    )
    (net (code "47") (name "Net-(DRV_Z-M2A)") (class "Default")
      (node (ref "DRV_Z") (pin "6") (pinfunction "M2A_6") (pintype "output"))
      (node (ref "J7") (pin "4") (pinfunction "4_4") (pintype "passive"))
    )
    (net (code "48") (name "Net-(DRV_Z-M2B)") (class "Default")
      (node (ref "DRV_Z") (pin "3") (pinfunction "M2B_3") (pintype "output"))
      (node (ref "J7") (pin "1") (pinfunction "1_1") (pintype "passive"))
    )
    (net (code "49") (name "Net-(J1-Pad1)") (class "Default")
      (node (ref "J1") (pin "1") (pinfunction "1_1") (pintype "passive"))
      (node (ref "J1") (pin "2") (pinfunction "2_2") (pintype "passive"))
      (node (ref "U$1") (pin "AGND") (pinfunction "AGND_AGND") (pintype "power_in"))
    )
    (net (code "50") (name "Net-(J10-Pad5)") (class "Default")
      (node (ref "J10") (pin "5") (pinfunction "5_5") (pintype "passive"))
      (node (ref "J10") (pin "6") (pinfunction "6_6") (pintype "passive"))
      (node (ref "R9") (pin "2") (pinfunction "2_2") (pintype "passive"))
      (node (ref "U$1") (pin "35") (pinfunction "35_35") (pintype "bidirectional"))
    )
    (net (code "51") (name "Net-(J10-Pad10)") (class "Default")
      (node (ref "J10") (pin "10") (pinfunction "10_10") (pintype "passive"))
      (node (ref "J10") (pin "9") (pinfunction "9_9") (pintype "passive"))
      (node (ref "U$1") (pin "37") (pinfunction "37_37") (pintype "bidirectional"))
    )
    (net (code "52") (name "Net-(J12-Pad1)") (class "Default")
      (node (ref "J12") (pin "1") (pinfunction "1_1") (pintype "passive"))
      (node (ref "J12") (pin "2") (pinfunction "2_2") (pintype "passive"))
      (node (ref "U$1") (pin "28") (pinfunction "28_28") (pintype "bidirectional"))
    )
    (net (code "53") (name "Net-(J12-Pad3)") (class "Default")
      (node (ref "J12") (pin "3") (pinfunction "3_3") (pintype "passive"))
      (node (ref "J12") (pin "4") (pinfunction "4_4") (pintype "passive"))
      (node (ref "U$1") (pin "29") (pinfunction "29_29") (pintype "bidirectional"))
    )
    (net (code "54") (name "Net-(U$1-0{slash}RX1)") (class "Default")
      (node (ref "J8") (pin "1") (pinfunction "1_1") (pintype "passive"))
      (node (ref "J8") (pin "2") (pinfunction "2_2") (pintype "passive"))
      (node (ref "U$1") (pin "0") (pinfunction "0/RX1_0") (pintype "bidirectional"))
    )
    (net (code "55") (name "Net-(U$1-7{slash}RX3)") (class "Default")
      (node (ref "J8") (pin "15") (pinfunction "15_15") (pintype "passive"))
      (node (ref "J8") (pin "16") (pinfunction "16_16") (pintype "passive"))
      (node (ref "U$1") (pin "7") (pinfunction "7/RX3_7") (pintype "bidirectional"))
    )
    (net (code "56") (name "Net-(U$1-8{slash}TX3)") (class "Default")
      (node (ref "J8") (pin "17") (pinfunction "17_17") (pintype "passive"))
      (node (ref "J8") (pin "18") (pinfunction "18_18") (pintype "passive"))
      (node (ref "U$1") (pin "8") (pinfunction "8/TX3_8") (pintype "bidirectional"))
    )
    (net (code "57") (name "Net-(U$1-9*{slash}RX2)") (class "Default")
      (node (ref "J8") (pin "19") (pinfunction "19_19") (pintype "passive"))
      (node (ref "J8") (pin "20") (pinfunction "20_20") (pintype "passive"))
      (node (ref "U$1") (pin "9") (pinfunction "9*/RX2_9") (pintype "bidirectional"))
    )
    (net (code "58") (name "Net-(U$1-17{slash}A3)") (class "Default")
      (node (ref "J9") (pin "10") (pinfunction "10_10") (pintype "passive"))
      (node (ref "J9") (pin "9") (pinfunction "9_9") (pintype "passive"))
      (node (ref "R8") (pin "1") (pinfunction "1_1") (pintype "passive"))
      (node (ref "U$1") (pin "17") (pinfunction "17/A3_17") (pintype "bidirectional"))
    )
    (net (code "59") (name "Net-(U$1-19{slash}A5{slash}SCL0)") (class "Default")
      (node (ref "J9") (pin "13") (pinfunction "13_13") (pintype "passive"))
      (node (ref "J9") (pin "14") (pinfunction "14_14") (pintype "passive"))
      (node (ref "U$1") (pin "19") (pinfunction "19/A5/SCL0_19") (pintype "bidirectional"))
    )
    (net (code "60") (name "Net-(U$1-20{slash}A6)") (class "Default")
      (node (ref "J9") (pin "15") (pinfunction "15_15") (pintype "passive"))
      (node (ref "J9") (pin "16") (pinfunction "16_16") (pintype "passive"))
      (node (ref "U$1") (pin "20") (pinfunction "20/A6_20") (pintype "bidirectional"))
    )
    (net (code "61") (name "Net-(U$1-23{slash}A9)") (class "Default")
      (node (ref "J2") (pin "1") (pinfunction "1_1") (pintype "passive"))
      (node (ref "J2") (pin "2") (pinfunction "2_2") (pintype "passive"))
      (node (ref "U$1") (pin "23") (pinfunction "23/A9_23") (pintype "bidirectional"))
    )
    (net (code "62") (name "Net-(U$1-24{slash}A10)") (class "Default")
      (node (ref "J11") (pin "1") (pinfunction "1_1") (pintype "passive"))
      (node (ref "J11") (pin "2") (pinfunction "2_2") (pintype "passive"))
      (node (ref "U$1") (pin "24") (pinfunction "24/A10_24") (pintype "bidirectional"))
    )
    (net (code "63") (name "Net-(U$1-25{slash}A11)") (class "Default")
      (node (ref "J11") (pin "3") (pinfunction "3_3") (pintype "passive"))
      (node (ref "J11") (pin "4") (pinfunction "4_4") (pintype "passive"))
      (node (ref "U$1") (pin "25") (pinfunction "25/A11_25") (pintype "bidirectional"))
    )
    (net (code "64") (name "Net-(U$1-38{slash}A14)") (class "Default")
      (node (ref "J10") (pin "11") (pinfunction "11_11") (pintype "passive"))
      (node (ref "J10") (pin "12") (pinfunction "12_12") (pintype "passive"))
      (node (ref "U$1") (pin "38") (pinfunction "38/A14_38") (pintype "bidirectional"))
    )
    (net (code "65") (name "Net-(U1-BOOT)") (class "Default")
      (node (ref "C9") (pin "1") (pinfunction "1_1") (pintype "passive"))
      (node (ref "U1") (pin "1") (pinfunction "BOOT_1") (pintype "output"))
    )
    (net (code "66") (name "Net-(U1-COMP)") (class "Default")
      (node (ref "C8") (pin "1") (pinfunction "1_1") (pintype "passive"))
      (node (ref "R24") (pin "2") (pinfunction "2_2") (pintype "passive"))
      (node (ref "U1") (pin "6") (pinfunction "COMP_6") (pintype "output"))
    )
    (net (code "67") (name "Net-(U1-FB)") (class "Default")
      (node (ref "R25") (pin "2") (pinfunction "2_2") (pintype "passive"))
      (node (ref "R26") (pin "1") (pinfunction "1_1") (pintype "passive"))
      (node (ref "U1") (pin "5") (pinfunction "FB_5") (pintype "input"))
    )
    (net (code "68") (name "Net-(U1-RT{slash}CLK)") (class "Default")
      (node (ref "R23") (pin "2") (pinfunction "2_2") (pintype "passive"))
      (node (ref "U1") (pin "4") (pinfunction "RT/CLK_4") (pintype "input"))
    )
    (net (code "69") (name "Net-(U1-SW)") (class "Default")
      (node (ref "C9") (pin "2") (pinfunction "2_2") (pintype "passive"))
      (node (ref "CR1") (pin "1") (pinfunction "1_1") (pintype "passive"))
      (node (ref "L1") (pin "1") (pinfunction "1_1") (pintype "passive"))
      (node (ref "U1") (pin "8") (pinfunction "SW_8") (pintype "input"))
    )
    (net (code "70") (name "unconnected-(DISPLAY-Pad7)") (class "Default")
      (node (ref "DISPLAY") (pin "7") (pinfunction "7_7") (pintype "passive"))
    )
    (net (code "71") (name "unconnected-(DISPLAY-Pad8)") (class "Default")
      (node (ref "DISPLAY") (pin "8") (pinfunction "8_8") (pintype "passive"))
    )
    (net (code "72") (name "unconnected-(DRV_X-CLK-Pad11)") (class "Default")
      (node (ref "DRV_X") (pin "11") (pinfunction "CLK_11") (pintype "bidirectional"))
    )
    (net (code "73") (name "unconnected-(DRV_X-DIAG-Pad18)") (class "Default")
      (node (ref "DRV_X") (pin "18") (pinfunction "DIAG_18") (pintype "output"))
    )
    (net (code "74") (name "unconnected-(DRV_X-INDEX-Pad17)") (class "Default")
      (node (ref "DRV_X") (pin "17") (pinfunction "INDEX_17") (pintype "output"))
    )
    (net (code "75") (name "unconnected-(DRV_X-MS1-Pad15)") (class "Default")
      (node (ref "DRV_X") (pin "15") (pinfunction "MS1_15") (pintype "input"))
    )
    (net (code "76") (name "unconnected-(DRV_X-MS2-Pad14)") (class "Default")
      (node (ref "DRV_X") (pin "14") (pinfunction "MS2_14") (pintype "input"))
    )
    (net (code "77") (name "unconnected-(DRV_X-TX-Pad12)") (class "Default")
      (node (ref "DRV_X") (pin "12") (pinfunction "TX_12") (pintype "bidirectional"))
    )
    (net (code "78") (name "unconnected-(DRV_Z-CLK-Pad11)") (class "Default")
      (node (ref "DRV_Z") (pin "11") (pinfunction "CLK_11") (pintype "bidirectional"))
    )
    (net (code "79") (name "unconnected-(DRV_Z-DIAG-Pad18)") (class "Default")
      (node (ref "DRV_Z") (pin "18") (pinfunction "DIAG_18") (pintype "output"))
    )
    (net (code "80") (name "unconnected-(DRV_Z-INDEX-Pad17)") (class "Default")
      (node (ref "DRV_Z") (pin "17") (pinfunction "INDEX_17") (pintype "output"))
    )
    (net (code "81") (name "unconnected-(DRV_Z-MS1-Pad15)") (class "Default")
      (node (ref "DRV_Z") (pin "15") (pinfunction "MS1_15") (pintype "input"))
    )
    (net (code "82") (name "unconnected-(DRV_Z-MS2-Pad14)") (class "Default")
      (node (ref "DRV_Z") (pin "14") (pinfunction "MS2_14") (pintype "input"))
    )
    (net (code "83") (name "unconnected-(DRV_Z-TX-Pad12)") (class "Default")
      (node (ref "DRV_Z") (pin "12") (pinfunction "TX_12") (pintype "bidirectional"))
    )
    (net (code "84") (name "unconnected-(U1-EN-Pad3)") (class "Default")
      (node (ref "U1") (pin "3") (pinfunction "EN_3") (pintype "input"))
    )
  )
)
